# ETH_on_RS485_Node_Example_RS485.net
KiCad netlist of a schematic drawn in Altium Designer
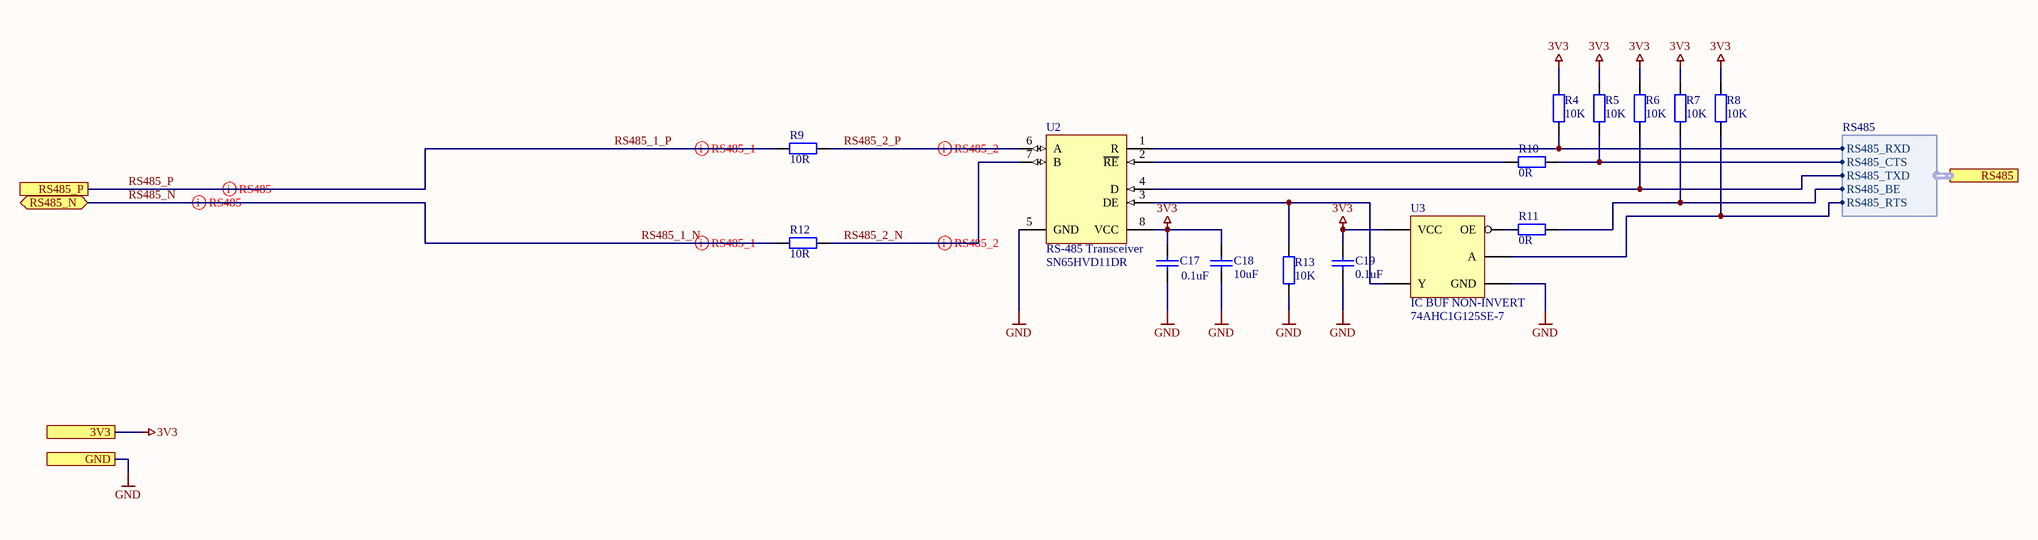
[diagram p0: ETH_on_RS485_Node_Example_RS485.SchDoc]

(export (version "E")
  (design (tool "Eeschema 10.0.6"))
  (components
    (comp (ref "C17")
      (value "0.1uF")
      (footprint "Ceramic Capacitor 0402 EIA")
      (description "SMD/SMT WCAP-CSGP 0.1uF 0402 20% 10V MLCC")
      (fields (field (name "TOLERANCE") "20%") (field (name "VOLTAGE") "10VDC"))
      (libsource (lib "RDM_Altium_Library") (part "Cap_0.1uF_0402"))
    )
    (comp (ref "C18")
      (value "10uF")
      (footprint "Ceramic Capacitor 0603 EIA")
      (description "SMD/SMT 0603 10uF 10volts")
      (fields (field (name "TOLERANCE") "20%") (field (name "VOLTAGE") "10VDC"))
      (libsource (lib "RDM_Altium_Library") (part "Cap_10uF_0603"))
    )
    (comp (ref "C19")
      (value "0.1uF")
      (footprint "Ceramic Capacitor 0402 EIA")
      (description "SMD/SMT WCAP-CSGP 0.1uF 0402 20% 10V MLCC")
      (fields (field (name "TOLERANCE") "20%") (field (name "VOLTAGE") "10VDC"))
      (libsource (lib "RDM_Altium_Library") (part "Cap_0.1uF_0402"))
    )
    (comp (ref "R4")
      (value "10K")
      (footprint "Resistor 0402 EIA")
      (description "SMD 10K ohm 1% 50V General Purpose")
      (fields (field (name "TOLERANCE") "1%") (field (name "POWER") "63mW"))
      (libsource (lib "RDM_Altium_Library") (part "Res_10K_0402"))
    )
    (comp (ref "R5")
      (value "10K")
      (footprint "Resistor 0402 EIA")
      (description "SMD 10K ohm 1% 50V General Purpose")
      (fields (field (name "TOLERANCE") "1%") (field (name "POWER") "63mW"))
      (libsource (lib "RDM_Altium_Library") (part "Res_10K_0402"))
    )
    (comp (ref "R6")
      (value "10K")
      (footprint "Resistor 0402 EIA")
      (description "SMD 10K ohm 1% 50V General Purpose")
      (fields (field (name "TOLERANCE") "1%") (field (name "POWER") "63mW"))
      (libsource (lib "RDM_Altium_Library") (part "Res_10K_0402"))
    )
    (comp (ref "R7")
      (value "10K")
      (footprint "Resistor 0402 EIA")
      (description "SMD 10K ohm 1% 50V General Purpose")
      (fields (field (name "TOLERANCE") "1%") (field (name "POWER") "63mW"))
      (libsource (lib "RDM_Altium_Library") (part "Res_10K_0402"))
    )
    (comp (ref "R8")
      (value "10K")
      (footprint "Resistor 0402 EIA")
      (description "SMD 10K ohm 1% 50V General Purpose")
      (fields (field (name "TOLERANCE") "1%") (field (name "POWER") "63mW"))
      (libsource (lib "RDM_Altium_Library") (part "Res_10K_0402"))
    )
    (comp (ref "R9")
      (value "10R")
      (footprint "Resistor 0603 EIA")
      (description "SMD 0603 10ohms 1%")
      (fields (field (name "TOLERANCE") "1%") (field (name "POWER") "250mW"))
      (libsource (lib "RDM_ALT_SCH") (part "Res_10R_0603"))
    )
    (comp (ref "R10")
      (value "0R")
      (footprint "Resistor 0402 EIA")
      (description "0 Ohms Resistor 0402")
      (fields (field (name "POWER") "100mW") (field (name "MANUFACTURER") "Panasonic Electronic Components"))
      (libsource (lib "RDM_ALT_SCH") (part "Res_0R_0402"))
    )
    (comp (ref "R11")
      (value "0R")
      (footprint "Resistor 0402 EIA")
      (description "0 Ohms Resistor 0402")
      (fields (field (name "POWER") "100mW") (field (name "MANUFACTURER") "Panasonic Electronic Components"))
      (libsource (lib "RDM_ALT_SCH") (part "Res_0R_0402"))
    )
    (comp (ref "R12")
      (value "10R")
      (footprint "Resistor 0603 EIA")
      (description "SMD 0603 10ohms 1%")
      (fields (field (name "TOLERANCE") "1%") (field (name "POWER") "250mW"))
      (libsource (lib "RDM_ALT_SCH") (part "Res_10R_0603"))
    )
    (comp (ref "R13")
      (value "10K")
      (footprint "Resistor 0402 EIA")
      (description "SMD 10K ohm 1% 50V General Purpose")
      (fields (field (name "TOLERANCE") "1%") (field (name "POWER") "63mW"))
      (libsource (lib "RDM_Altium_Library") (part "Res_10K_0402"))
    )
    (comp (ref "U2")
      (value "RS-485 Transceiver")
      (footprint "TI_D (R-PDSO-G8)_8_R")
      (description "RS-485 Interface IC 3.3V Differential Transceivers")
      (fields
        (field (name "MANUFACTURER") "Texas Instruments")
        (field (name "MANUFACTURER PARTNR") "SN65HVD11DR")
      )
      (libsource (lib "RDM_Altium_Library") (part "SN65HVD11DR"))
    )
    (comp (ref "U3")
      (value "IC BUF NON-INVERT")
      (footprint "SOT353")
      (description "Buffer, Non-Inverting 1 Element 1 Bit per Element 3-State Output SOT-353")
      (fields
        (field (name "MANUFACTURER") "Diodes Incorporated")
        (field (name "MANUFACTURER PARTNR") "74AHC1G125SE-7")
      )
      (libsource (lib "RDM_Altium_Library") (part "74AHC1G125SE-7"))
    )
  )
  (nets
    (net (code "2") (name "/RS485_1_N") (class "Default")
      (node (ref "R12") (pin "1") (pinfunction "1_1") (pintype "passive"))
    )
    (net (code "3") (name "/RS485_1_P") (class "Default")
      (node (ref "R9") (pin "1") (pinfunction "1_1") (pintype "passive"))
    )
    (net (code "4") (name "/RS485_2_N") (class "Default")
      (node (ref "R12") (pin "2") (pinfunction "2_2") (pintype "passive"))
      (node (ref "U2") (pin "7") (pinfunction "B_7") (pintype "bidirectional"))
    )
    (net (code "5") (name "/RS485_2_P") (class "Default")
      (node (ref "R9") (pin "2") (pinfunction "2_2") (pintype "passive"))
      (node (ref "U2") (pin "6") (pinfunction "A_6") (pintype "bidirectional"))
    )
    (net (code "7") (name "3V3") (class "Default")
      (node (ref "C17") (pin "1") (pinfunction "1_1") (pintype "passive"))
      (node (ref "C18") (pin "2") (pinfunction "2_2") (pintype "passive"))
      (node (ref "C19") (pin "1") (pinfunction "1_1") (pintype "passive"))
      (node (ref "R4") (pin "2") (pinfunction "2_2") (pintype "passive"))
      (node (ref "R5") (pin "2") (pinfunction "2_2") (pintype "passive"))
      (node (ref "R6") (pin "2") (pinfunction "2_2") (pintype "passive"))
      (node (ref "R7") (pin "2") (pinfunction "2_2") (pintype "passive"))
      (node (ref "R8") (pin "2") (pinfunction "2_2") (pintype "passive"))
      (node (ref "U2") (pin "8") (pinfunction "VCC_8") (pintype "power_in"))
      (node (ref "U3") (pin "5") (pinfunction "VCC_5") (pintype "passive"))
    )
    (net (code "8") (name "GND") (class "Default")
      (node (ref "C17") (pin "2") (pinfunction "2_2") (pintype "passive"))
      (node (ref "C18") (pin "1") (pinfunction "1_1") (pintype "passive"))
      (node (ref "C19") (pin "2") (pinfunction "2_2") (pintype "passive"))
      (node (ref "R13") (pin "1") (pinfunction "1_1") (pintype "passive"))
      (node (ref "U2") (pin "5") (pinfunction "GND_5") (pintype "power_in"))
      (node (ref "U3") (pin "3") (pinfunction "GND_3") (pintype "passive"))
    )
    (net (code "9") (name "Net-(R10-Pad2)") (class "Default")
      (node (ref "R10") (pin "2") (pinfunction "2_2") (pintype "passive"))
      (node (ref "R5") (pin "1") (pinfunction "1_1") (pintype "passive"))
    )
    (net (code "10") (name "Net-(R11-Pad2)") (class "Default")
      (node (ref "R11") (pin "2") (pinfunction "2_2") (pintype "passive"))
      (node (ref "R7") (pin "1") (pinfunction "1_1") (pintype "passive"))
    )
    (net (code "11") (name "Net-(U2-D)") (class "Default")
      (node (ref "R6") (pin "1") (pinfunction "1_1") (pintype "passive"))
      (node (ref "U2") (pin "4") (pinfunction "D_4") (pintype "input"))
    )
    (net (code "12") (name "Net-(U2-DE)") (class "Default")
      (node (ref "R13") (pin "2") (pinfunction "2_2") (pintype "passive"))
      (node (ref "U2") (pin "3") (pinfunction "DE_3") (pintype "input"))
      (node (ref "U3") (pin "4") (pinfunction "Y_4") (pintype "passive"))
    )
    (net (code "13") (name "Net-(U2-R)") (class "Default")
      (node (ref "R4") (pin "1") (pinfunction "1_1") (pintype "passive"))
      (node (ref "U2") (pin "1") (pinfunction "R_1") (pintype "tri_state"))
    )
    (net (code "14") (name "Net-(U2-~{RE})") (class "Default")
      (node (ref "R10") (pin "1") (pinfunction "1_1") (pintype "passive"))
      (node (ref "U2") (pin "2") (pinfunction "~{RE}_2") (pintype "input"))
    )
    (net (code "15") (name "Net-(U3-A)") (class "Default")
      (node (ref "R8") (pin "1") (pinfunction "1_1") (pintype "passive"))
      (node (ref "U3") (pin "2") (pinfunction "A_2") (pintype "passive"))
    )
    (net (code "16") (name "Net-(U3-OE)") (class "Default")
      (node (ref "R11") (pin "1") (pinfunction "1_1") (pintype "passive"))
      (node (ref "U3") (pin "1") (pinfunction "OE_1") (pintype "passive"))
    )
  )
)
